# IOB-Signal.net
KiCad netlist of a schematic drawn in EAGLE
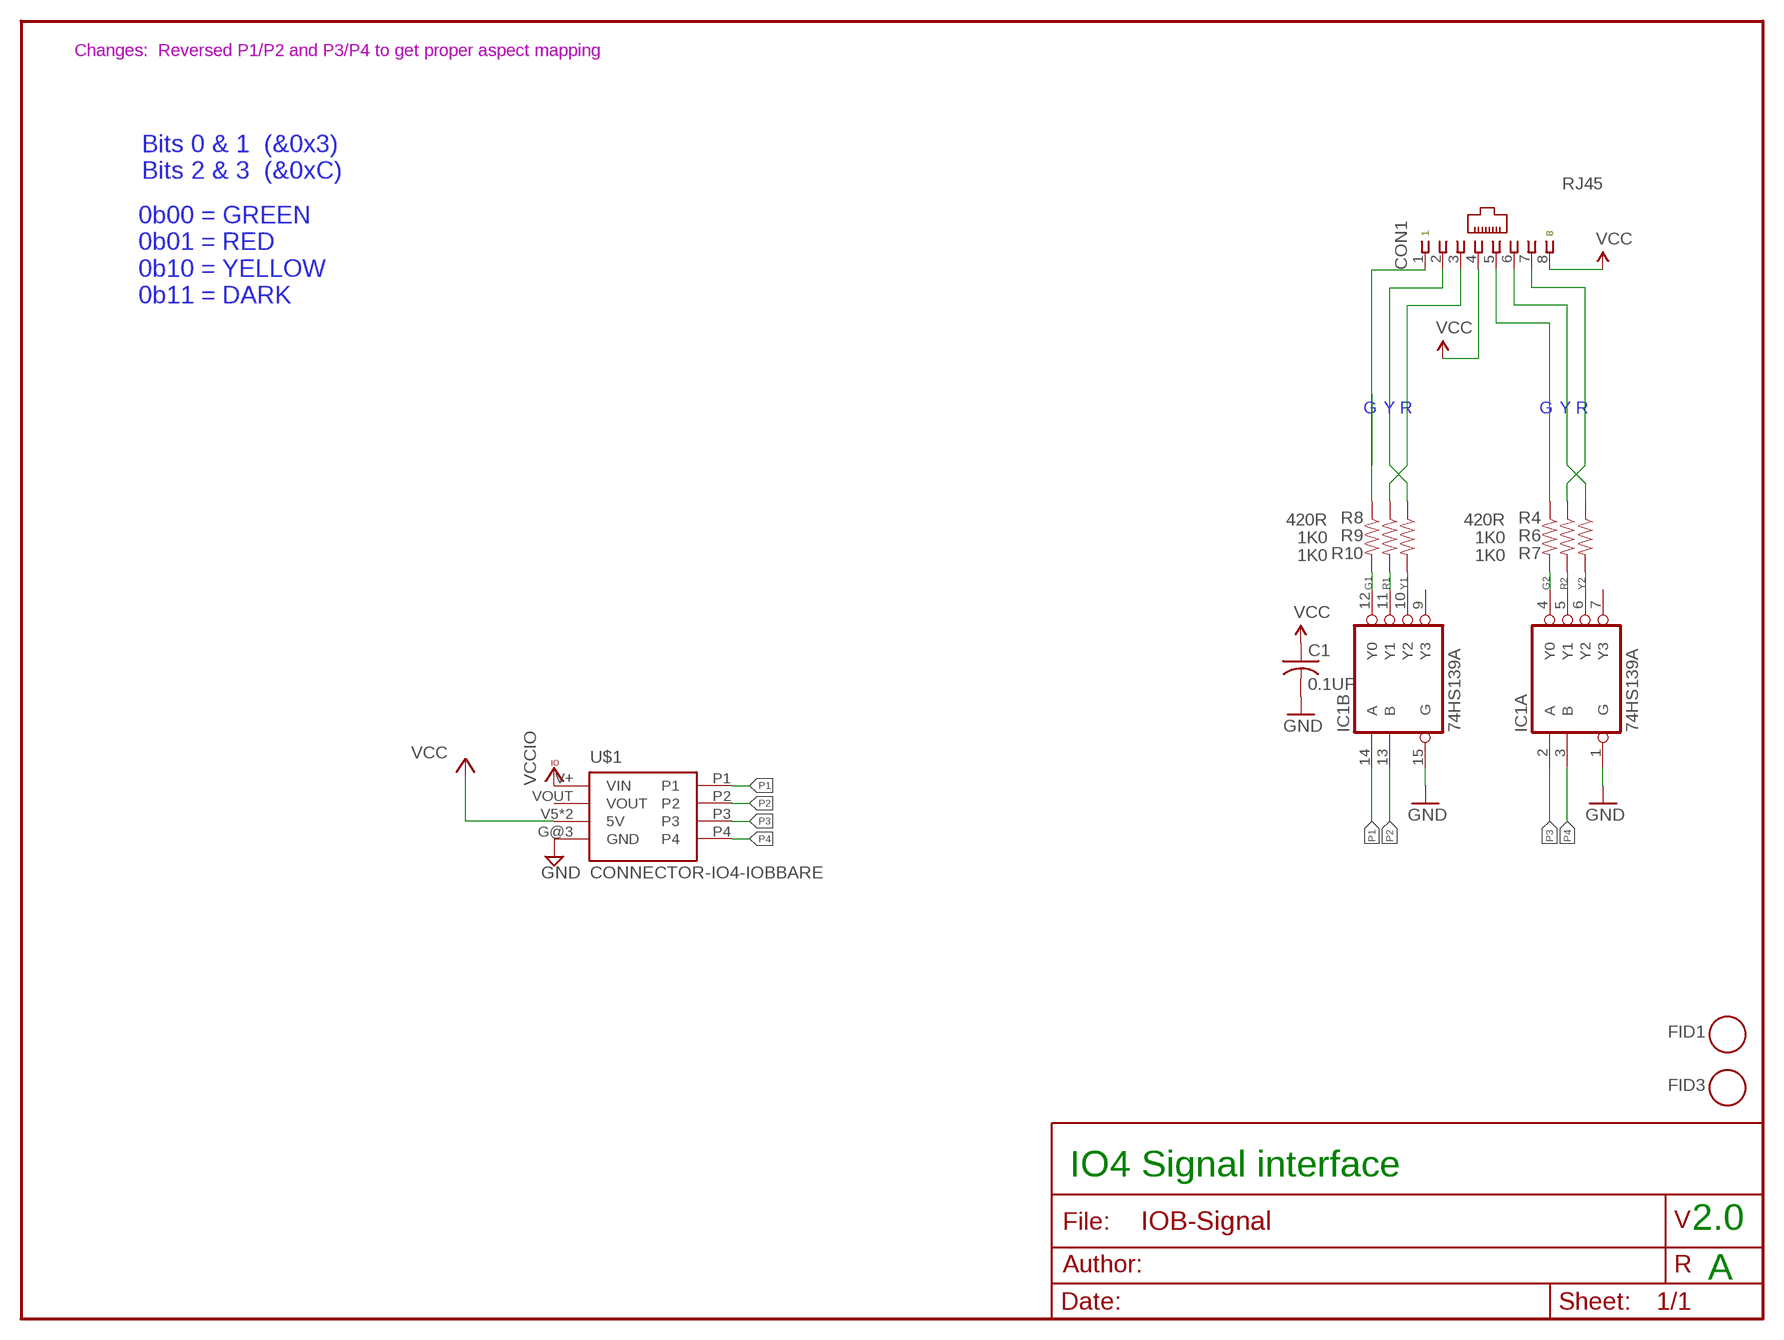
[diagram p0: schematic, sheet 1]

(export (version "E")
  (design (tool "Eeschema 10.0.6"))
  (components
    (comp (ref "C1")
      (value "0.1UF")
      (footprint "eagle-import:0805-CAP")
      (libsource (lib "eagle-import") (part "CAP0805"))
    )
    (comp (ref "CON1")
      (value "RJ45")
      (footprint "eagle-import:RJ45-NO-SHIELD")
      (libsource (lib "eagle-import") (part "CONNECTOR-RJ45-FRONT"))
    )
    (comp (ref "FID1")
      (value "FIDUCIAL")
      (footprint "eagle-import:FIDUCIAL_1MM")
      (libsource (lib "eagle-import") (part "FIDUCIAL"))
    )
    (comp (ref "FID3")
      (value "FIDUCIAL")
      (footprint "eagle-import:FIDUCIAL_1MM")
      (libsource (lib "eagle-import") (part "FIDUCIAL"))
    )
    (comp (ref "IC1")
      (value "74HS139A")
      (footprint "eagle-import:SO16")
      (libsource (lib "eagle-import") (part "74139DLS"))
    )
    (comp (ref "R4")
      (value "420R")
      (footprint "eagle-import:0805-RES")
      (libsource (lib "eagle-import") (part "R0805-RES"))
    )
    (comp (ref "R6")
      (value "1K0")
      (footprint "eagle-import:0805-RES")
      (libsource (lib "eagle-import") (part "R0805-RES"))
    )
    (comp (ref "R7")
      (value "1K0")
      (footprint "eagle-import:0805-RES")
      (libsource (lib "eagle-import") (part "R0805-RES"))
    )
    (comp (ref "R8")
      (value "420R")
      (footprint "eagle-import:0805-RES")
      (libsource (lib "eagle-import") (part "R0805-RES"))
    )
    (comp (ref "R9")
      (value "1K0")
      (footprint "eagle-import:0805-RES")
      (libsource (lib "eagle-import") (part "R0805-RES"))
    )
    (comp (ref "R10")
      (value "1K0")
      (footprint "eagle-import:0805-RES")
      (libsource (lib "eagle-import") (part "R0805-RES"))
    )
    (comp (ref "U$1")
      (value "CONNECTOR-IO4-IOBBARE")
      (footprint "eagle-import:IO4-IOB")
      (libsource (lib "eagle-import") (part "CONNECTOR-IO4-IOBBARE"))
    )
  )
  (nets
    (net (code "1") (name "/G1") (class "Default")
      (node (ref "IC1") (pin "12") (pinfunction "Y0_12") (pintype "output"))
      (node (ref "R10") (pin "2") (pinfunction "2_2") (pintype "passive"))
    )
    (net (code "2") (name "/G2") (class "Default")
      (node (ref "IC1") (pin "4") (pinfunction "Y0_4") (pintype "output"))
      (node (ref "R7") (pin "2") (pinfunction "2_2") (pintype "passive"))
    )
    (net (code "3") (name "/R1") (class "Default")
      (node (ref "IC1") (pin "11") (pinfunction "Y1_11") (pintype "output"))
      (node (ref "R9") (pin "2") (pinfunction "2_2") (pintype "passive"))
    )
    (net (code "4") (name "/R2") (class "Default")
      (node (ref "IC1") (pin "5") (pinfunction "Y1_5") (pintype "output"))
      (node (ref "R6") (pin "2") (pinfunction "2_2") (pintype "passive"))
    )
    (net (code "5") (name "/VOUT") (class "Default")
      (node (ref "U$1") (pin "VOUT") (pinfunction "VOUT_VOUT") (pintype "power_in"))
    )
    (net (code "6") (name "/Y1") (class "Default")
      (node (ref "IC1") (pin "10") (pinfunction "Y2_10") (pintype "output"))
      (node (ref "R8") (pin "2") (pinfunction "2_2") (pintype "passive"))
    )
    (net (code "7") (name "/Y2") (class "Default")
      (node (ref "IC1") (pin "6") (pinfunction "Y2_6") (pintype "output"))
      (node (ref "R4") (pin "2") (pinfunction "2_2") (pintype "passive"))
    )
    (net (code "8") (name "GND") (class "Default")
      (node (ref "C1") (pin "2") (pinfunction "2_2") (pintype "passive"))
      (node (ref "IC1") (pin "1") (pinfunction "G_1") (pintype "input"))
      (node (ref "IC1") (pin "15") (pinfunction "G_15") (pintype "input"))
      (node (ref "U$1") (pin "G@3") (pinfunction "GND_G@3") (pintype "power_in"))
    )
    (net (code "9") (name "Net-(CON1-Pad1)") (class "Default")
      (node (ref "CON1") (pin "1") (pinfunction "1_1") (pintype "passive"))
      (node (ref "R10") (pin "1") (pinfunction "1_1") (pintype "passive"))
    )
    (net (code "10") (name "Net-(CON1-Pad2)") (class "Default")
      (node (ref "CON1") (pin "2") (pinfunction "2_2") (pintype "passive"))
      (node (ref "R8") (pin "1") (pinfunction "1_1") (pintype "passive"))
    )
    (net (code "11") (name "Net-(CON1-Pad3)") (class "Default")
      (node (ref "CON1") (pin "3") (pinfunction "3_3") (pintype "passive"))
      (node (ref "R9") (pin "1") (pinfunction "1_1") (pintype "passive"))
    )
    (net (code "12") (name "Net-(CON1-Pad5)") (class "Default")
      (node (ref "CON1") (pin "5") (pinfunction "5_5") (pintype "passive"))
      (node (ref "R7") (pin "1") (pinfunction "1_1") (pintype "passive"))
    )
    (net (code "13") (name "Net-(CON1-Pad6)") (class "Default")
      (node (ref "CON1") (pin "6") (pinfunction "6_6") (pintype "passive"))
      (node (ref "R4") (pin "1") (pinfunction "1_1") (pintype "passive"))
    )
    (net (code "14") (name "Net-(CON1-Pad7)") (class "Default")
      (node (ref "CON1") (pin "7") (pinfunction "7_7") (pintype "passive"))
      (node (ref "R6") (pin "1") (pinfunction "1_1") (pintype "passive"))
    )
    (net (code "15") (name "P1") (class "Default")
      (node (ref "IC1") (pin "14") (pinfunction "A_14") (pintype "input"))
      (node (ref "U$1") (pin "P1") (pinfunction "P1_P1") (pintype "bidirectional"))
    )
    (net (code "16") (name "P2") (class "Default")
      (node (ref "IC1") (pin "13") (pinfunction "B_13") (pintype "input"))
      (node (ref "U$1") (pin "P2") (pinfunction "P2_P2") (pintype "bidirectional"))
    )
    (net (code "17") (name "P3") (class "Default")
      (node (ref "IC1") (pin "2") (pinfunction "A_2") (pintype "input"))
      (node (ref "U$1") (pin "P3") (pinfunction "P3_P3") (pintype "bidirectional"))
    )
    (net (code "18") (name "P4") (class "Default")
      (node (ref "IC1") (pin "3") (pinfunction "B_3") (pintype "input"))
      (node (ref "U$1") (pin "P4") (pinfunction "P4_P4") (pintype "bidirectional"))
    )
    (net (code "19") (name "VCC") (class "Default")
      (node (ref "C1") (pin "1") (pinfunction "1_1") (pintype "passive"))
      (node (ref "CON1") (pin "4") (pinfunction "4_4") (pintype "passive"))
      (node (ref "CON1") (pin "8") (pinfunction "8_8") (pintype "passive"))
      (node (ref "U$1") (pin "V5") (pinfunction "5V_V5") (pintype "power_in"))
      (node (ref "U$1") (pin "V5@1") (pinfunction "5V_V5@1") (pintype "power_in"))
    )
    (net (code "20") (name "VCCIO") (class "Default")
      (node (ref "U$1") (pin "V+") (pinfunction "VIN_V+") (pintype "power_in"))
    )
    (net (code "21") (name "unconnected-(IC1A-Y3-Pad7)") (class "Default")
      (node (ref "IC1") (pin "7") (pinfunction "Y3_7") (pintype "output"))
    )
    (net (code "22") (name "unconnected-(IC1B-Y3-Pad9)") (class "Default")
      (node (ref "IC1") (pin "9") (pinfunction "Y3_9") (pintype "output"))
    )
  )
)
